# PowerSupply.net
KiCad netlist of a schematic drawn in Altium Designer
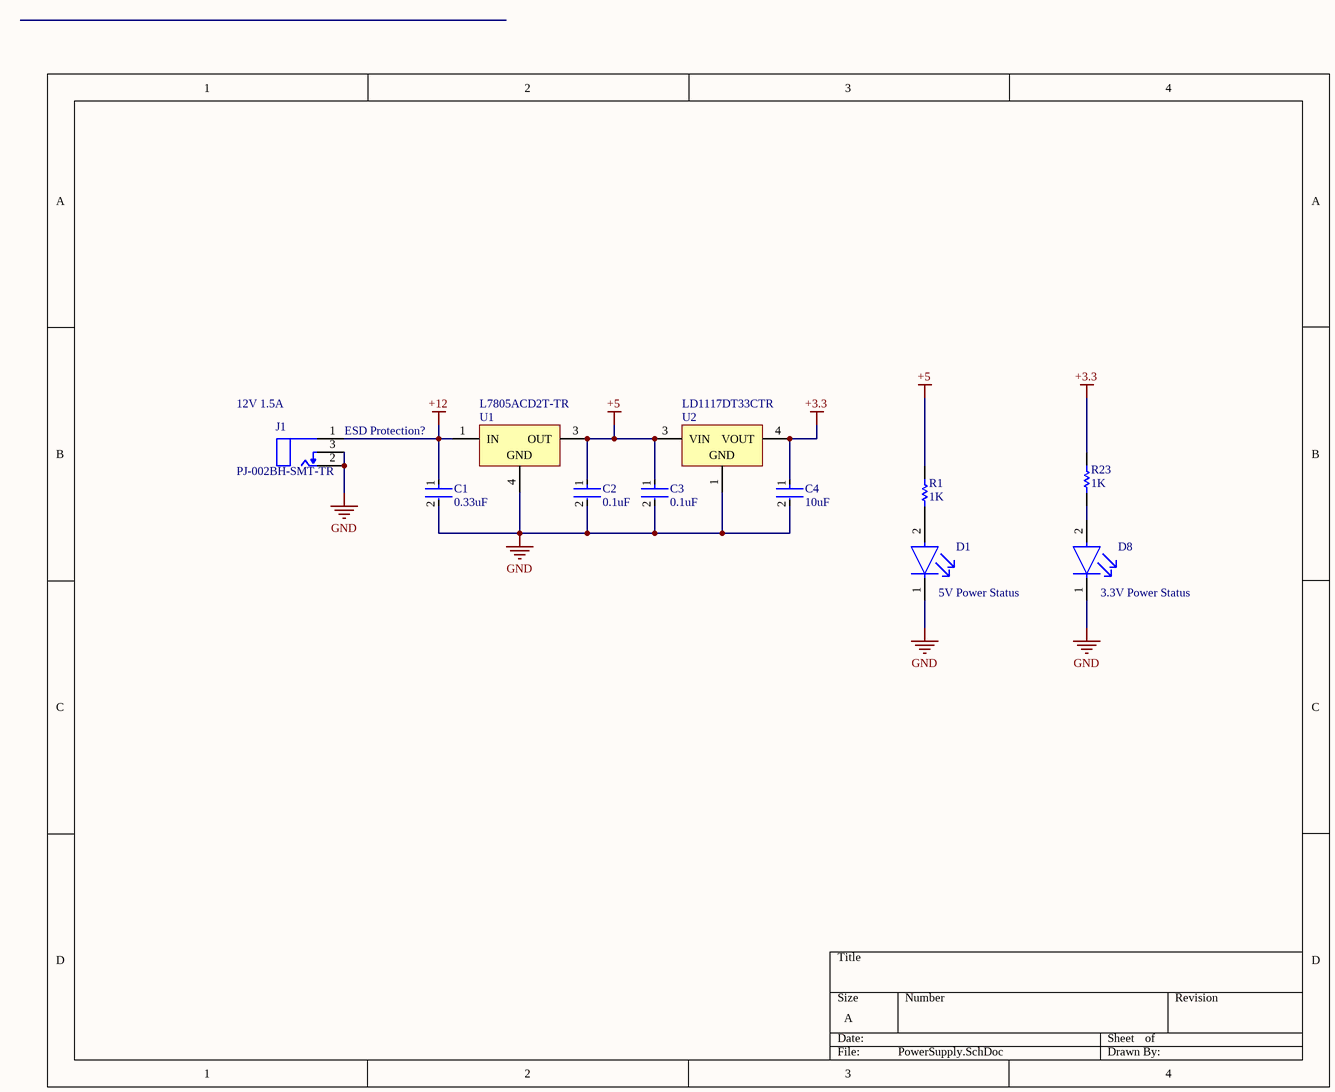
[diagram p0: PowerSupply.SchDoc]

(export (version "E")
  (design (tool "Eeschema 10.0.6"))
  (components
    (comp (ref "C1")
      (value "0.33uF")
      (footprint "FP-C0805C-DN-MFG")
      (description "CAP CER 0.33UF 50V X7R 0805")
      (fields
        (field (name "MANUFACTURER PART NUMBER") "C0805C334K5RACTU")
        (field (name "MANUFACTURER") "KEMET")
      )
      (libsource (lib "Altium Content Vault") (part "b4654b650e69147ec39a6b967a45e02"))
    )
    (comp (ref "C2")
      (value "0.1uF")
      (footprint "FP-C0805C-DN-MFG")
      (description "CAP CER 0.1UF 50V X7R 0805")
      (fields
        (field (name "MANUFACTURER PART NUMBER") "C0805C104K5RACTU")
        (field (name "MANUFACTURER") "KEMET")
      )
      (libsource (lib "Altium Content Vault") (part "b4654b650e69147ec39a6b967a45e02"))
    )
    (comp (ref "C3")
      (value "0.1uF")
      (footprint "FP-C0805C-DN-MFG")
      (description "CAP CER 0.1UF 50V X7R 0805")
      (fields
        (field (name "MANUFACTURER PART NUMBER") "C0805C104K5RACTU")
        (field (name "MANUFACTURER") "KEMET")
      )
      (libsource (lib "Altium Content Vault") (part "b4654b650e69147ec39a6b967a45e02"))
    )
    (comp (ref "C4")
      (value "10uF")
      (footprint "FP-C0805C-DG-MFG")
      (description "CAP CER 10UF 10V X5R 0805")
      (fields (field (name "TOLERANCE") "10%") (field (name "MANUFACTURER PART NUMBER") "C0805C106K8PACTU"))
      (libsource (lib "Altium Content Vault") (part "11868f565c42a9108669ba33697ecf6"))
    )
    (comp (ref "D1")
      (value "5V Power Status")
      (footprint "FP-LTST-C191TBKT-MFG")
      (description "LED BLUE CLEAR CHIP SMD")
      (libsource (lib "Altium Content Vault") (part "8706943c75ba83719d021d2fdc84c58"))
    )
    (comp (ref "D8")
      (value "3.3V Power Status")
      (footprint "FP-LTST-C191TBKT-MFG")
      (description "LED BLUE CLEAR CHIP SMD")
      (libsource (lib "Altium Content Vault") (part "8706943c75ba83719d021d2fdc84c58"))
    )
    (comp (ref "J1")
      (value "PJ-002BH-SMT-TR")
      (footprint "FP-PJ-002BH-SMT-TR-MFG")
      (description "CONN PWR JACK 2.5X5.5MM SOLDER")
      (fields
        (field (name "MANUFACTURER") "CUI Inc")
        (field (name "OCTOPART") "https://octopart.com/pj-002bh-smt-tr-cui-25947151")
      )
      (libsource (lib "Altium Content Vault") (part "020ff674638626da6de6501228ee46e"))
    )
    (comp (ref "R1")
      (value "1K")
      (footprint "RESC2013X50X30NL20T20")
      (fields (field (name "PART NUMBER") "CRCW08051K00FKEA") (field (name "MANUFACTURER") "Vishay Dale"))
      (libsource (lib "Altium Content Vault") (part "RES"))
    )
    (comp (ref "R23")
      (value "1K")
      (footprint "RESC2013X50X30NL20T20")
      (fields (field (name "PART NUMBER") "CRCW08051K00FKEA") (field (name "MANUFACTURER") "Vishay Dale"))
      (libsource (lib "Altium Content Vault") (part "RES"))
    )
    (comp (ref "U1")
      (value "L7805ACD2T-TR")
      (footprint "TO-263_N")
      (description "Positive Voltage Regulator, 3-Pin D2PAK, Tape and Reel")
      (libsource (lib "Altium Content Vault") (part "PM-REG-L4940-SOT3"))
    )
    (comp (ref "U2")
      (value "LD1117DT33CTR")
      (footprint "TO-252_M")
      (description "Fixed Low Drop Positive Voltage Regulator, 3.3V, 3-Pin DPAK, Tape and Reel")
      (libsource (lib "Altium Content Vault") (part "PM-REG-LD1117-SOT3"))
    )
  )
  (nets
    (net (code "1") (name "+3.3") (class "Default")
      (node (ref "C4") (pin "1") (pinfunction "1_1") (pintype "passive"))
      (node (ref "R23") (pin "2") (pinfunction "2_2") (pintype "passive"))
      (node (ref "U2") (pin "4") (pinfunction "VOUT_4") (pintype "power_in"))
    )
    (net (code "2") (name "+5") (class "Default")
      (node (ref "C2") (pin "1") (pinfunction "1_1") (pintype "passive"))
      (node (ref "C3") (pin "1") (pinfunction "1_1") (pintype "passive"))
      (node (ref "R1") (pin "2") (pinfunction "2_2") (pintype "passive"))
      (node (ref "U1") (pin "3") (pinfunction "OUT_3") (pintype "power_in"))
      (node (ref "U2") (pin "3") (pinfunction "VIN_3") (pintype "power_in"))
    )
    (net (code "3") (name "+12") (class "Default")
      (node (ref "C1") (pin "1") (pinfunction "1_1") (pintype "passive"))
      (node (ref "J1") (pin "1") (pinfunction "1_1") (pintype "passive"))
      (node (ref "U1") (pin "1") (pinfunction "IN_1") (pintype "power_in"))
    )
    (net (code "4") (name "GND") (class "Default")
      (node (ref "C1") (pin "2") (pinfunction "2_2") (pintype "passive"))
      (node (ref "C2") (pin "2") (pinfunction "2_2") (pintype "passive"))
      (node (ref "C3") (pin "2") (pinfunction "2_2") (pintype "passive"))
      (node (ref "C4") (pin "2") (pinfunction "2_2") (pintype "passive"))
      (node (ref "D1") (pin "1") (pinfunction "C_1") (pintype "passive"))
      (node (ref "D8") (pin "1") (pinfunction "C_1") (pintype "passive"))
      (node (ref "J1") (pin "2") (pinfunction "2_2") (pintype "passive"))
      (node (ref "J1") (pin "3") (pinfunction "3_3") (pintype "passive"))
      (node (ref "U1") (pin "4") (pinfunction "GND_4") (pintype "power_in"))
      (node (ref "U2") (pin "1") (pinfunction "GND_1") (pintype "power_in"))
    )
    (net (code "5") (name "Net-(D1-A)") (class "Default")
      (node (ref "D1") (pin "2") (pinfunction "A_2") (pintype "passive"))
      (node (ref "R1") (pin "1") (pinfunction "1_1") (pintype "passive"))
    )
    (net (code "6") (name "Net-(D8-A)") (class "Default")
      (node (ref "D8") (pin "2") (pinfunction "A_2") (pintype "passive"))
      (node (ref "R23") (pin "1") (pinfunction "1_1") (pintype "passive"))
    )
  )
)
